# LC_LPF6.net
KiCad netlist of a schematic drawn in Altium Designer
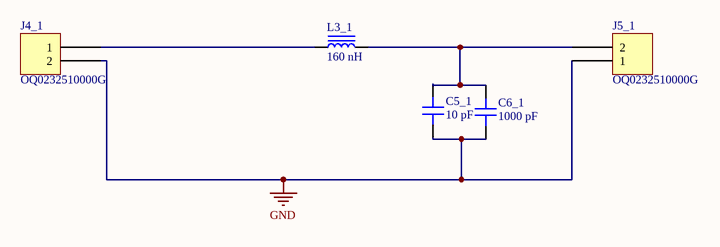
[diagram p0: LC_LPF6.SchDoc]

(export (version "E")
  (design (tool "Eeschema 10.0.6"))
  (components
    (comp (ref "C5_1")
      (value "10 pF")
      (footprint "CAP 0603_1608")
      (description "CAP CER 10PF 100V C0G/NPO 0603")
      (fields (field (name "PART NUMBER") "AC0603JRNPO0BN100") (field (name "MANUFACTURER") "Yageo"))
      (libsource (lib "Celestial Altium Library - altium_library") (part "Capacitor"))
    )
    (comp (ref "C6_1")
      (value "1000 pF")
      (footprint "CAP 0603_1608")
      (description "CAP CER 1000PF 100V X7R 0603")
      (fields
        (field (name "PART NUMBER") "GCD188R72A102KA01D")
        (field (name "MANUFACTURER") "Murata Electronics")
      )
      (libsource (lib "Celestial Altium Library - altium_library") (part "Capacitor"))
    )
    (comp (ref "J4_1")
      (value "OQ0232510000G")
      (footprint "FCI 06-381-2PIN")
      (description "TERM BLOCK HDR 2POS 90DEG 3.81MM")
      (fields (field (name "MANUFACTURER") "Amphenol Anytek"))
      (libsource (lib "Celestial Altium Library - altium_library") (part "2 Pin"))
    )
    (comp (ref "J5_1")
      (value "OQ0232510000G")
      (footprint "FCI 06-381-2PIN")
      (description "TERM BLOCK HDR 2POS 90DEG 3.81MM")
      (fields (field (name "MANUFACTURER") "Amphenol Anytek"))
      (libsource (lib "") (part "2 Pin_1"))
    )
    (comp (ref "L3_1")
      (value "160 nH")
      (footprint "IND 0402_1005 RF WW")
      (description "FIXED IND 160NH 480MA 330MOHM SM")
      (fields
        (field (name "PART NUMBER") "LQW15CNR16J00D")
        (field (name "MANUFACTURER") "Murata Electronics")
      )
      (libsource (lib "Celestial Altium Library - altium_library") (part "Inductor"))
    )
  )
  (nets
    (net (code "1") (name "GND") (class "Default")
      (node (ref "C5_1") (pin "1") (pinfunction "1_1") (pintype "passive"))
      (node (ref "C6_1") (pin "2") (pinfunction "2_2") (pintype "passive"))
      (node (ref "J4_1") (pin "2") (pinfunction "2_2") (pintype "passive"))
      (node (ref "J5_1") (pin "1") (pinfunction "1_1") (pintype "passive"))
    )
    (net (code "2") (name "Net-(C5_1-Pad2)") (class "Default")
      (node (ref "C5_1") (pin "2") (pinfunction "2_2") (pintype "passive"))
      (node (ref "C6_1") (pin "1") (pinfunction "1_1") (pintype "passive"))
      (node (ref "J5_1") (pin "2") (pinfunction "2_2") (pintype "passive"))
      (node (ref "L3_1") (pin "2") (pinfunction "2_2") (pintype "passive"))
    )
    (net (code "3") (name "Net-(J4_1-Pad1)") (class "Default")
      (node (ref "J4_1") (pin "1") (pinfunction "1_1") (pintype "passive"))
      (node (ref "L3_1") (pin "1") (pinfunction "1_1") (pintype "passive"))
    )
  )
)
